# ili9327.net
KiCad netlist of a schematic drawn in Altium Designer
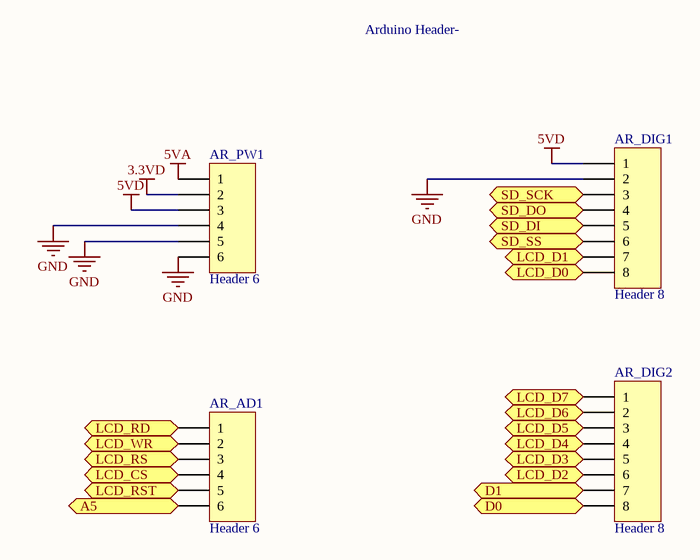
[diagram p0: ili9327.SchDoc]

(export (version "E")
  (design (tool "Eeschema 10.0.6"))
  (components
    (comp (ref "AR_AD1")
      (value "Header 6")
      (footprint "HDR1X6")
      (description "Header, 6-Pin")
      (fields (field (name "PUBLISHER") "Altium Limited"))
      (libsource (lib "Miscellaneous Connectors") (part "Header 6"))
    )
    (comp (ref "AR_DIG1")
      (value "Header 8")
      (footprint "HDR1X8")
      (description "Header, 8-Pin")
      (fields (field (name "PUBLISHER") "Altium Limited"))
      (libsource (lib "Miscellaneous Connectors") (part "Header 8"))
    )
    (comp (ref "AR_DIG2")
      (value "Header 8")
      (footprint "HDR1X8")
      (description "Header, 8-Pin")
      (fields (field (name "PUBLISHER") "Altium Limited"))
      (libsource (lib "Miscellaneous Connectors") (part "Header 8"))
    )
    (comp (ref "AR_PW1")
      (value "Header 6")
      (footprint "HDR1X6")
      (description "Header, 6-Pin")
      (fields (field (name "PUBLISHER") "Altium Limited"))
      (libsource (lib "Miscellaneous Connectors") (part "Header 6"))
    )
  )
  (nets
    (net (code "1") (name "/A5") (class "Default")
      (node (ref "AR_AD1") (pin "6") (pinfunction "6_6") (pintype "passive"))
    )
    (net (code "2") (name "/D0") (class "Default")
      (node (ref "AR_DIG2") (pin "8") (pinfunction "8_8") (pintype "passive"))
    )
    (net (code "3") (name "/D1") (class "Default")
      (node (ref "AR_DIG2") (pin "7") (pinfunction "7_7") (pintype "passive"))
    )
    (net (code "4") (name "/LCD_CS") (class "Default")
      (node (ref "AR_AD1") (pin "4") (pinfunction "4_4") (pintype "passive"))
    )
    (net (code "5") (name "/LCD_D0") (class "Default")
      (node (ref "AR_DIG1") (pin "8") (pinfunction "8_8") (pintype "passive"))
    )
    (net (code "6") (name "/LCD_D1") (class "Default")
      (node (ref "AR_DIG1") (pin "7") (pinfunction "7_7") (pintype "passive"))
    )
    (net (code "7") (name "/LCD_D2") (class "Default")
      (node (ref "AR_DIG2") (pin "6") (pinfunction "6_6") (pintype "passive"))
    )
    (net (code "8") (name "/LCD_D3") (class "Default")
      (node (ref "AR_DIG2") (pin "5") (pinfunction "5_5") (pintype "passive"))
    )
    (net (code "9") (name "/LCD_D4") (class "Default")
      (node (ref "AR_DIG2") (pin "4") (pinfunction "4_4") (pintype "passive"))
    )
    (net (code "10") (name "/LCD_D5") (class "Default")
      (node (ref "AR_DIG2") (pin "3") (pinfunction "3_3") (pintype "passive"))
    )
    (net (code "11") (name "/LCD_D6") (class "Default")
      (node (ref "AR_DIG2") (pin "2") (pinfunction "2_2") (pintype "passive"))
    )
    (net (code "12") (name "/LCD_D7") (class "Default")
      (node (ref "AR_DIG2") (pin "1") (pinfunction "1_1") (pintype "passive"))
    )
    (net (code "13") (name "/LCD_RD") (class "Default")
      (node (ref "AR_AD1") (pin "1") (pinfunction "1_1") (pintype "passive"))
    )
    (net (code "14") (name "/LCD_RS") (class "Default")
      (node (ref "AR_AD1") (pin "3") (pinfunction "3_3") (pintype "passive"))
    )
    (net (code "15") (name "/LCD_RST") (class "Default")
      (node (ref "AR_AD1") (pin "5") (pinfunction "5_5") (pintype "passive"))
    )
    (net (code "16") (name "/LCD_WR") (class "Default")
      (node (ref "AR_AD1") (pin "2") (pinfunction "2_2") (pintype "passive"))
    )
    (net (code "17") (name "/SD_DI") (class "Default")
      (node (ref "AR_DIG1") (pin "5") (pinfunction "5_5") (pintype "passive"))
    )
    (net (code "18") (name "/SD_DO") (class "Default")
      (node (ref "AR_DIG1") (pin "4") (pinfunction "4_4") (pintype "passive"))
    )
    (net (code "19") (name "/SD_SCK") (class "Default")
      (node (ref "AR_DIG1") (pin "3") (pinfunction "3_3") (pintype "passive"))
    )
    (net (code "20") (name "/SD_SS") (class "Default")
      (node (ref "AR_DIG1") (pin "6") (pinfunction "6_6") (pintype "passive"))
    )
    (net (code "21") (name "3.3VD") (class "Default")
      (node (ref "AR_PW1") (pin "2") (pinfunction "2_2") (pintype "passive"))
    )
    (net (code "22") (name "5VA") (class "Default")
      (node (ref "AR_PW1") (pin "1") (pinfunction "1_1") (pintype "passive"))
    )
    (net (code "23") (name "5VD") (class "Default")
      (node (ref "AR_DIG1") (pin "1") (pinfunction "1_1") (pintype "passive"))
      (node (ref "AR_PW1") (pin "3") (pinfunction "3_3") (pintype "passive"))
    )
    (net (code "24") (name "GND") (class "Default")
      (node (ref "AR_DIG1") (pin "2") (pinfunction "2_2") (pintype "passive"))
      (node (ref "AR_PW1") (pin "4") (pinfunction "4_4") (pintype "passive"))
      (node (ref "AR_PW1") (pin "5") (pinfunction "5_5") (pintype "passive"))
      (node (ref "AR_PW1") (pin "6") (pinfunction "6_6") (pintype "passive"))
    )
  )
)
